# 07_-_NAND_FLASH.net
KiCad netlist of a schematic drawn in Altium Designer
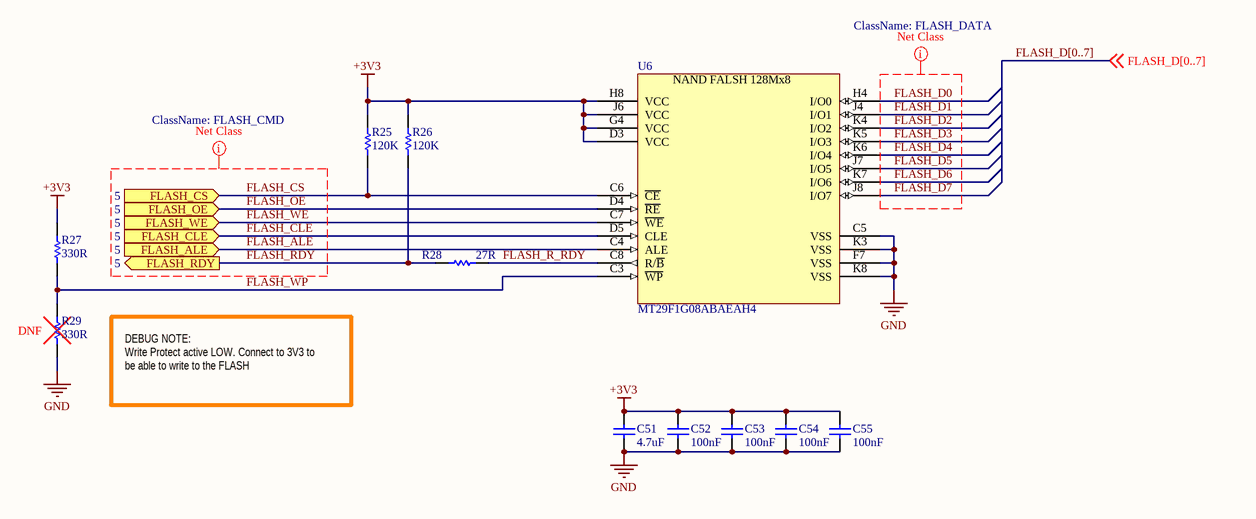
[diagram p0: [07] - NAND FLASH.SchDoc]

(export (version "E")
  (design (tool "Eeschema 10.0.6"))
  (components
    (comp (ref "C51")
      (value "4.7uF")
      (footprint "CAP-0805")
      (description "Multilayer Ceramic Capacitors MLCC - SMD/SMT WCAP-CSGP 4.7uF 0805 20% 16V MLCC")
      (fields (field (name "MANUFACTURER") "Wurth Elektronik") (field (name "Comment") "885012107013"))
      (libsource (lib "Linux-Capable-Business-Card") (part "CAP-0805-4.7u-885012107013_2"))
    )
    (comp (ref "C52")
      (value "100nF")
      (footprint "CAP-0603")
      (description "Multilayer Ceramic Capacitors MLCC - SMD/SMT 16V 0.1uF X7R 0603 20%")
      (fields (field (name "MANUFACTURER") "KEMET") (field (name "Comment") "C0603C104M4RAC"))
      (libsource (lib "Linux-Capable-Business-Card") (part "CAP-0603-100n-C0603C104M4RAC"))
    )
    (comp (ref "C53")
      (value "100nF")
      (footprint "CAP-0603")
      (description "Multilayer Ceramic Capacitors MLCC - SMD/SMT 16V 0.1uF X7R 0603 20%")
      (fields (field (name "MANUFACTURER") "KEMET") (field (name "Comment") "C0603C104M4RAC"))
      (libsource (lib "Linux-Capable-Business-Card") (part "CAP-0603-100n-C0603C104M4RAC"))
    )
    (comp (ref "C54")
      (value "100nF")
      (footprint "CAP-0603")
      (description "Multilayer Ceramic Capacitors MLCC - SMD/SMT 16V 0.1uF X7R 0603 20%")
      (fields (field (name "MANUFACTURER") "KEMET") (field (name "Comment") "C0603C104M4RAC"))
      (libsource (lib "Linux-Capable-Business-Card") (part "CAP-0603-100n-C0603C104M4RAC"))
    )
    (comp (ref "C55")
      (value "100nF")
      (footprint "CAP-0603")
      (description "Multilayer Ceramic Capacitors MLCC - SMD/SMT 16V 0.1uF X7R 0603 20%")
      (fields (field (name "MANUFACTURER") "KEMET") (field (name "Comment") "C0603C104M4RAC"))
      (libsource (lib "Linux-Capable-Business-Card") (part "CAP-0603-100n-C0603C104M4RAC"))
    )
    (comp (ref "R25")
      (value "120K")
      (footprint "RES-0603")
      (description "Thin Film Resistors - SMD 1/10W 120K ohm 1% 50ppm")
      (fields (field (name "MANUFACTURER") "Yageo") (field (name "Comment") "RT0603FRE07120KL"))
      (libsource (lib "Linux-Capable-Business-Card") (part "RES-0603-120K-RT0603FRE07120KL"))
    )
    (comp (ref "R26")
      (value "120K")
      (footprint "RES-0603")
      (description "Thin Film Resistors - SMD 1/10W 120K ohm 1% 50ppm")
      (fields (field (name "MANUFACTURER") "Yageo") (field (name "Comment") "RT0603FRE07120KL"))
      (libsource (lib "Linux-Capable-Business-Card") (part "RES-0603-120K-RT0603FRE07120KL"))
    )
    (comp (ref "R27")
      (value "330R")
      (footprint "RES-0603")
      (description "Thin Film Resistors - SMD 1/10W 330 ohm 1% 50ppm")
      (fields (field (name "MANUFACTURER") "Yageo") (field (name "Comment") "RT0603FRD07330RL"))
      (libsource (lib "Linux-Capable-Business-Card") (part "RES-0603-330R-RT0603FRD07330RL"))
    )
    (comp (ref "R28")
      (value "27R")
      (footprint "RES-0603")
      (description "Thin Film Resistors - SMD 1/10W 27 ohm 1% 50ppm")
      (fields (field (name "MANUFACTURER") "Yageo") (field (name "Comment") "RT0603DRD0727RL"))
      (libsource (lib "Linux-Capable-Business-Card") (part "RES-0603-27R-RT0603DRD0727RL"))
    )
    (comp (ref "R29")
      (value "330R")
      (footprint "RES-0603")
      (description "Thin Film Resistors - SMD 1/10W 330 ohm 1% 50ppm")
      (fields (field (name "MANUFACTURER") "Yageo") (field (name "Comment") "RT0603FRD07330RL"))
      (libsource (lib "Linux-Capable-Business-Card") (part "RES-0603-330R-RT0603FRD07330RL"))
    )
    (comp (ref "U6")
      (value "MT29F1G08ABAEAH4")
      (footprint "BGA0.8_FLASH_63_9X11")
      (description "NAND Flash SLC 1G 128MX8 VFBGA-63")
      (libsource (lib "Linux-Capable-Business-Card") (part "MICRON-FLASH-MT29F1G08ABAEAH4"))
    )
  )
  (nets
    (net (code "1") (name "+3V3") (class "Default")
      (node (ref "C51") (pin "2") (pinfunction "2_2") (pintype "passive"))
      (node (ref "C52") (pin "2") (pinfunction "2_2") (pintype "passive"))
      (node (ref "C53") (pin "2") (pinfunction "2_2") (pintype "passive"))
      (node (ref "C54") (pin "2") (pinfunction "2_2") (pintype "passive"))
      (node (ref "C55") (pin "2") (pinfunction "2_2") (pintype "passive"))
      (node (ref "R25") (pin "2") (pinfunction "2_2") (pintype "passive"))
      (node (ref "R26") (pin "2") (pinfunction "2_2") (pintype "passive"))
      (node (ref "R27") (pin "2") (pinfunction "2_2") (pintype "passive"))
      (node (ref "U6") (pin "D3") (pinfunction "VCC_D3") (pintype "power_in"))
      (node (ref "U6") (pin "G4") (pinfunction "VCC_G4") (pintype "power_in"))
      (node (ref "U6") (pin "H8") (pinfunction "VCC_H8") (pintype "power_in"))
      (node (ref "U6") (pin "J6") (pinfunction "VCC_J6") (pintype "power_in"))
    )
    (net (code "2") (name "/FLASH_ALE") (class "Default")
      (node (ref "U6") (pin "C4") (pinfunction "ALE_C4") (pintype "input"))
    )
    (net (code "3") (name "/FLASH_CLE") (class "Default")
      (node (ref "U6") (pin "D5") (pinfunction "CLE_D5") (pintype "input"))
    )
    (net (code "4") (name "/FLASH_CS") (class "Default")
      (node (ref "R25") (pin "1") (pinfunction "1_1") (pintype "passive"))
      (node (ref "U6") (pin "C6") (pinfunction "~{CE}_C6") (pintype "input"))
    )
    (net (code "5") (name "/FLASH_OE") (class "Default")
      (node (ref "U6") (pin "D4") (pinfunction "~{RE}_D4") (pintype "input"))
    )
    (net (code "6") (name "/FLASH_RDY") (class "Default")
      (node (ref "R26") (pin "1") (pinfunction "1_1") (pintype "passive"))
      (node (ref "R28") (pin "1") (pinfunction "1_1") (pintype "passive"))
    )
    (net (code "7") (name "/FLASH_R_RDY") (class "Default")
      (node (ref "R28") (pin "2") (pinfunction "2_2") (pintype "passive"))
      (node (ref "U6") (pin "C8") (pinfunction "R/~{B}_C8") (pintype "output"))
    )
    (net (code "8") (name "/FLASH_WE") (class "Default")
      (node (ref "U6") (pin "C7") (pinfunction "~{WE}_C7") (pintype "input"))
    )
    (net (code "9") (name "/FLASH_WP") (class "Default")
      (node (ref "R27") (pin "1") (pinfunction "1_1") (pintype "passive"))
      (node (ref "R29") (pin "2") (pinfunction "2_2") (pintype "passive"))
      (node (ref "U6") (pin "C3") (pinfunction "~{WP}_C3") (pintype "input"))
    )
    (net (code "10") (name "FLASH_D0") (class "Default")
      (node (ref "U6") (pin "H4") (pinfunction "I/O0_H4") (pintype "bidirectional"))
    )
    (net (code "11") (name "FLASH_D1") (class "Default")
      (node (ref "U6") (pin "J4") (pinfunction "I/O1_J4") (pintype "bidirectional"))
    )
    (net (code "12") (name "FLASH_D2") (class "Default")
      (node (ref "U6") (pin "K4") (pinfunction "I/O2_K4") (pintype "bidirectional"))
    )
    (net (code "13") (name "FLASH_D3") (class "Default")
      (node (ref "U6") (pin "K5") (pinfunction "I/O3_K5") (pintype "bidirectional"))
    )
    (net (code "14") (name "FLASH_D4") (class "Default")
      (node (ref "U6") (pin "K6") (pinfunction "I/O4_K6") (pintype "bidirectional"))
    )
    (net (code "15") (name "FLASH_D5") (class "Default")
      (node (ref "U6") (pin "J7") (pinfunction "I/O5_J7") (pintype "bidirectional"))
    )
    (net (code "16") (name "FLASH_D6") (class "Default")
      (node (ref "U6") (pin "K7") (pinfunction "I/O6_K7") (pintype "bidirectional"))
    )
    (net (code "17") (name "FLASH_D7") (class "Default")
      (node (ref "U6") (pin "J8") (pinfunction "I/O7_J8") (pintype "bidirectional"))
    )
    (net (code "19") (name "GND") (class "Default")
      (node (ref "C51") (pin "1") (pinfunction "1_1") (pintype "passive"))
      (node (ref "C52") (pin "1") (pinfunction "1_1") (pintype "passive"))
      (node (ref "C53") (pin "1") (pinfunction "1_1") (pintype "passive"))
      (node (ref "C54") (pin "1") (pinfunction "1_1") (pintype "passive"))
      (node (ref "C55") (pin "1") (pinfunction "1_1") (pintype "passive"))
      (node (ref "R29") (pin "1") (pinfunction "1_1") (pintype "passive"))
      (node (ref "U6") (pin "C5") (pinfunction "VSS_C5") (pintype "power_in"))
      (node (ref "U6") (pin "F7") (pinfunction "VSS_F7") (pintype "power_in"))
      (node (ref "U6") (pin "K3") (pinfunction "VSS_K3") (pintype "power_in"))
      (node (ref "U6") (pin "K8") (pinfunction "VSS_K8") (pintype "power_in"))
    )
  )
)
